# PLL.net
KiCad netlist of a schematic drawn in Altium Designer
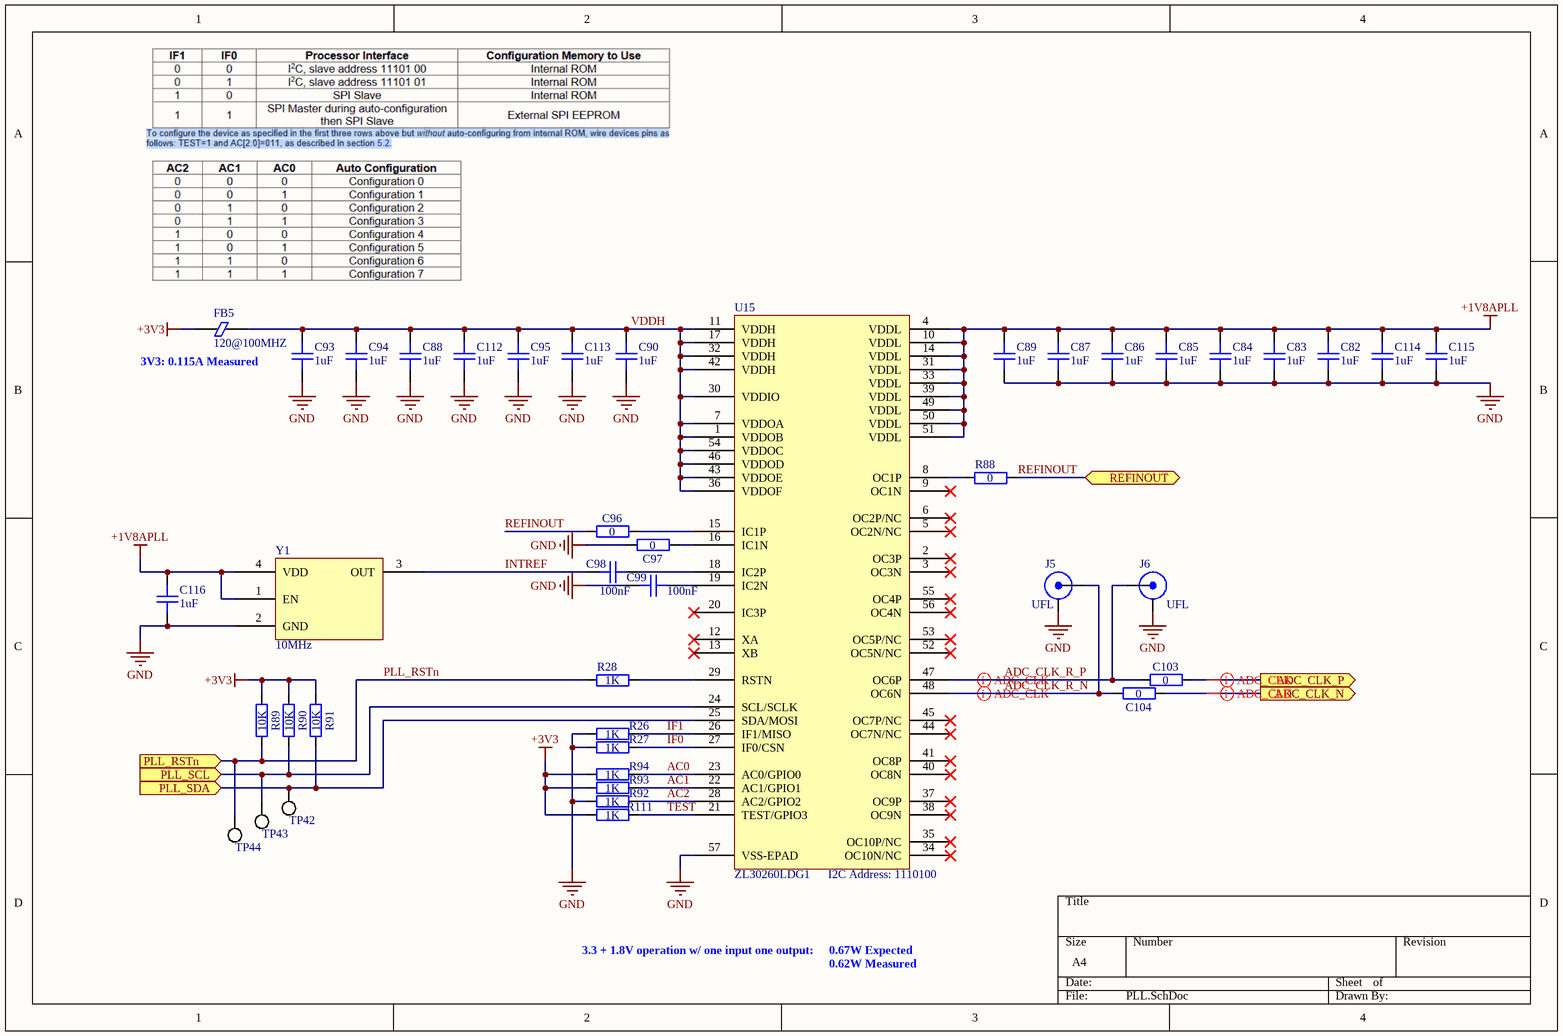
[diagram p0: PLL.SchDoc]

(export (version "E")
  (design (tool "Eeschema 10.0.6"))
  (components
    (comp (ref "C82")
      (value "1uF")
      (footprint "GEN_C_0402")
      (fields
        (field (name "MANUFACTURER") "Murata")
        (field (name "MANUFACTURER PART NUMBER") "GRM155R61E105KA12D")
      )
      (libsource (lib "DSO") (part "CAP 1uF 25V X5R 0402"))
    )
    (comp (ref "C83")
      (value "1uF")
      (footprint "GEN_C_0402")
      (fields
        (field (name "MANUFACTURER") "Murata")
        (field (name "MANUFACTURER PART NUMBER") "GRM155R61E105KA12D")
      )
      (libsource (lib "DSO") (part "CAP 1uF 25V X5R 0402"))
    )
    (comp (ref "C84")
      (value "1uF")
      (footprint "GEN_C_0402")
      (fields
        (field (name "MANUFACTURER") "Murata")
        (field (name "MANUFACTURER PART NUMBER") "GRM155R61E105KA12D")
      )
      (libsource (lib "DSO") (part "CAP 1uF 25V X5R 0402"))
    )
    (comp (ref "C85")
      (value "1uF")
      (footprint "GEN_C_0402")
      (fields
        (field (name "MANUFACTURER") "Murata")
        (field (name "MANUFACTURER PART NUMBER") "GRM155R61E105KA12D")
      )
      (libsource (lib "DSO") (part "CAP 1uF 25V X5R 0402"))
    )
    (comp (ref "C86")
      (value "1uF")
      (footprint "GEN_C_0402")
      (fields
        (field (name "MANUFACTURER") "Murata")
        (field (name "MANUFACTURER PART NUMBER") "GRM155R61E105KA12D")
      )
      (libsource (lib "DSO") (part "CAP 1uF 25V X5R 0402"))
    )
    (comp (ref "C87")
      (value "1uF")
      (footprint "GEN_C_0402")
      (fields
        (field (name "MANUFACTURER") "Murata")
        (field (name "MANUFACTURER PART NUMBER") "GRM155R61E105KA12D")
      )
      (libsource (lib "DSO") (part "CAP 1uF 25V X5R 0402"))
    )
    (comp (ref "C88")
      (value "1uF")
      (footprint "GEN_C_0402")
      (fields
        (field (name "MANUFACTURER") "Murata")
        (field (name "MANUFACTURER PART NUMBER") "GRM155R61E105KA12D")
      )
      (libsource (lib "DSO") (part "CAP 1uF 25V X5R 0402"))
    )
    (comp (ref "C89")
      (value "1uF")
      (footprint "GEN_C_0402")
      (fields
        (field (name "MANUFACTURER") "Murata")
        (field (name "MANUFACTURER PART NUMBER") "GRM155R61E105KA12D")
      )
      (libsource (lib "DSO") (part "CAP 1uF 25V X5R 0402"))
    )
    (comp (ref "C90")
      (value "1uF")
      (footprint "GEN_C_0402")
      (fields
        (field (name "MANUFACTURER") "Murata")
        (field (name "MANUFACTURER PART NUMBER") "GRM155R61E105KA12D")
      )
      (libsource (lib "DSO") (part "CAP 1uF 25V X5R 0402"))
    )
    (comp (ref "C93")
      (value "1uF")
      (footprint "GEN_C_0402")
      (fields
        (field (name "MANUFACTURER") "Murata")
        (field (name "MANUFACTURER PART NUMBER") "GRM155R61E105KA12D")
      )
      (libsource (lib "DSO") (part "CAP 1uF 25V X5R 0402"))
    )
    (comp (ref "C94")
      (value "1uF")
      (footprint "GEN_C_0402")
      (fields
        (field (name "MANUFACTURER") "Murata")
        (field (name "MANUFACTURER PART NUMBER") "GRM155R61E105KA12D")
      )
      (libsource (lib "DSO") (part "CAP 1uF 25V X5R 0402"))
    )
    (comp (ref "C95")
      (value "1uF")
      (footprint "GEN_C_0402")
      (fields
        (field (name "MANUFACTURER") "Murata")
        (field (name "MANUFACTURER PART NUMBER") "GRM155R61E105KA12D")
      )
      (libsource (lib "DSO") (part "CAP 1uF 25V X5R 0402"))
    )
    (comp (ref "C96")
      (value "0")
      (footprint "GEN_R_0402")
      (fields
        (field (name "MANUFACTURER") "Yageo")
        (field (name "MANUFACTURER PART NUMBER") "RC0402JR-070RL")
      )
      (libsource (lib "DSO") (part "RES 0 OHM 1/16W 0402"))
    )
    (comp (ref "C97")
      (value "0")
      (footprint "GEN_R_0402")
      (fields
        (field (name "MANUFACTURER") "Yageo")
        (field (name "MANUFACTURER PART NUMBER") "RC0402JR-070RL")
      )
      (libsource (lib "DSO") (part "RES 0 OHM 1/16W 0402"))
    )
    (comp (ref "C98")
      (value "100nF")
      (footprint "GEN_C_0402")
      (fields
        (field (name "HOUSE PART NUMBER") "C-100nF-0402-002")
        (field (name "MANUFACTURER") "Murata")
        (field (name "MANUFACTURER PART NUMBER") "GCM155R71C104KA55D")
      )
      (libsource (lib "DSO") (part "CAP 100nF 16V X7R 0402"))
    )
    (comp (ref "C99")
      (value "100nF")
      (footprint "GEN_C_0402")
      (fields
        (field (name "HOUSE PART NUMBER") "C-100nF-0402-002")
        (field (name "MANUFACTURER") "Murata")
        (field (name "MANUFACTURER PART NUMBER") "GCM155R71C104KA55D")
      )
      (libsource (lib "DSO") (part "CAP 100nF 16V X7R 0402"))
    )
    (comp (ref "C103")
      (value "0")
      (footprint "GEN_R_0402")
      (fields
        (field (name "MANUFACTURER") "Yageo")
        (field (name "MANUFACTURER PART NUMBER") "RC0402JR-070RL")
      )
      (libsource (lib "DSO") (part "RES 0 OHM 1/16W 0402"))
    )
    (comp (ref "C104")
      (value "0")
      (footprint "GEN_R_0402")
      (fields
        (field (name "MANUFACTURER") "Yageo")
        (field (name "MANUFACTURER PART NUMBER") "RC0402JR-070RL")
      )
      (libsource (lib "DSO") (part "RES 0 OHM 1/16W 0402"))
    )
    (comp (ref "C112")
      (value "1uF")
      (footprint "GEN_C_0402")
      (fields
        (field (name "MANUFACTURER") "Murata")
        (field (name "MANUFACTURER PART NUMBER") "GRM155R61E105KA12D")
      )
      (libsource (lib "DSO") (part "CAP 1uF 25V X5R 0402"))
    )
    (comp (ref "C113")
      (value "1uF")
      (footprint "GEN_C_0402")
      (fields
        (field (name "MANUFACTURER") "Murata")
        (field (name "MANUFACTURER PART NUMBER") "GRM155R61E105KA12D")
      )
      (libsource (lib "DSO") (part "CAP 1uF 25V X5R 0402"))
    )
    (comp (ref "C114")
      (value "1uF")
      (footprint "GEN_C_0402")
      (fields
        (field (name "MANUFACTURER") "Murata")
        (field (name "MANUFACTURER PART NUMBER") "GRM155R61E105KA12D")
      )
      (libsource (lib "DSO") (part "CAP 1uF 25V X5R 0402"))
    )
    (comp (ref "C115")
      (value "1uF")
      (footprint "GEN_C_0402")
      (fields
        (field (name "MANUFACTURER") "Murata")
        (field (name "MANUFACTURER PART NUMBER") "GRM155R61E105KA12D")
      )
      (libsource (lib "DSO") (part "CAP 1uF 25V X5R 0402"))
    )
    (comp (ref "C116")
      (value "1uF")
      (footprint "GEN_C_0402")
      (fields
        (field (name "MANUFACTURER") "Murata")
        (field (name "MANUFACTURER PART NUMBER") "GRM155R61E105KA12D")
      )
      (libsource (lib "DSO") (part "CAP 1uF 25V X5R 0402"))
    )
    (comp (ref "FB5")
      (value "120@100MHZ")
      (footprint "GEN_R_0402")
      (fields (field (name "HOUSE PART NUMBER") "BLM15PX121SN1D") (field (name "MANUFACTURER") "Murata"))
      (libsource (lib "DSO") (part "FERRITE BEAD 120 OHM 0402"))
    )
    (comp (ref "J5")
      (value "UFL")
      (footprint "TE_2334884-1")
      (fields
        (field (name "MANUFACTURER") "TE Connectivity")
        (field (name "MANUFACTURER PART NUMBER") "2334884-1")
      )
      (libsource (lib "DSO") (part "UFL Jack SMD"))
    )
    (comp (ref "J6")
      (value "UFL")
      (footprint "TE_2334884-1")
      (fields
        (field (name "MANUFACTURER") "TE Connectivity")
        (field (name "MANUFACTURER PART NUMBER") "2334884-1")
      )
      (libsource (lib "DSO") (part "UFL Jack SMD"))
    )
    (comp (ref "R26")
      (value "1K")
      (footprint "GEN_R_0402")
      (fields
        (field (name "TOLERANCE") "1%")
        (field (name "MANUFACTURER") "Yageo")
        (field (name "HOUSE PART NUMBER") "R-1K-0402-1%-001")
      )
      (libsource (lib "DSO") (part "RES 1K OHM 1% 1/10W 0402"))
    )
    (comp (ref "R27")
      (value "1K")
      (footprint "GEN_R_0402")
      (fields
        (field (name "TOLERANCE") "1%")
        (field (name "MANUFACTURER") "Yageo")
        (field (name "HOUSE PART NUMBER") "R-1K-0402-1%-001")
      )
      (libsource (lib "DSO") (part "RES 1K OHM 1% 1/10W 0402"))
    )
    (comp (ref "R28")
      (value "1K")
      (footprint "GEN_R_0402")
      (fields
        (field (name "TOLERANCE") "1%")
        (field (name "MANUFACTURER") "Yageo")
        (field (name "HOUSE PART NUMBER") "R-1K-0402-1%-001")
      )
      (libsource (lib "") (part "RES 1K OHM 1% 1/10W 0402_1"))
    )
    (comp (ref "R88")
      (value "0")
      (footprint "GEN_R_0402")
      (fields
        (field (name "MANUFACTURER") "Yageo")
        (field (name "MANUFACTURER PART NUMBER") "RC0402JR-070RL")
      )
      (libsource (lib "") (part "RES 0 OHM 1/16W 0402_1"))
    )
    (comp (ref "R89")
      (value "10K")
      (footprint "GEN_R_0402")
      (fields
        (field (name "TOLERANCE") "1%")
        (field (name "MANUFACTURER") "Panasonic")
        (field (name "MANUFACTURER PART NUMBER") "ERJ-2RKF1002X")
      )
      (libsource (lib "DSO") (part "RES 10K OHM 1% 1/10W 0402"))
    )
    (comp (ref "R90")
      (value "10K")
      (footprint "GEN_R_0402")
      (fields
        (field (name "TOLERANCE") "1%")
        (field (name "MANUFACTURER") "Panasonic")
        (field (name "MANUFACTURER PART NUMBER") "ERJ-2RKF1002X")
      )
      (libsource (lib "DSO") (part "RES 10K OHM 1% 1/10W 0402"))
    )
    (comp (ref "R91")
      (value "10K")
      (footprint "GEN_R_0402")
      (fields
        (field (name "TOLERANCE") "1%")
        (field (name "MANUFACTURER") "Panasonic")
        (field (name "MANUFACTURER PART NUMBER") "ERJ-2RKF1002X")
      )
      (libsource (lib "DSO") (part "RES 10K OHM 1% 1/10W 0402"))
    )
    (comp (ref "R92")
      (value "1K")
      (footprint "GEN_R_0402")
      (fields
        (field (name "TOLERANCE") "1%")
        (field (name "MANUFACTURER") "Yageo")
        (field (name "HOUSE PART NUMBER") "R-1K-0402-1%-001")
      )
      (libsource (lib "DSO") (part "RES 1K OHM 1% 1/10W 0402"))
    )
    (comp (ref "R93")
      (value "1K")
      (footprint "GEN_R_0402")
      (fields
        (field (name "TOLERANCE") "1%")
        (field (name "MANUFACTURER") "Yageo")
        (field (name "HOUSE PART NUMBER") "R-1K-0402-1%-001")
      )
      (libsource (lib "DSO") (part "RES 1K OHM 1% 1/10W 0402"))
    )
    (comp (ref "R94")
      (value "1K")
      (footprint "GEN_R_0402")
      (fields
        (field (name "TOLERANCE") "1%")
        (field (name "MANUFACTURER") "Yageo")
        (field (name "HOUSE PART NUMBER") "R-1K-0402-1%-001")
      )
      (libsource (lib "DSO") (part "RES 1K OHM 1% 1/10W 0402"))
    )
    (comp (ref "R111")
      (value "1K")
      (footprint "GEN_R_0402")
      (fields
        (field (name "TOLERANCE") "1%")
        (field (name "MANUFACTURER") "Yageo")
        (field (name "HOUSE PART NUMBER") "R-1K-0402-1%-001")
      )
      (libsource (lib "DSO") (part "RES 1K OHM 1% 1/10W 0402"))
    )
    (comp (ref "TP42") (value "PCB") (footprint "GEN_TP_PCB") (libsource (lib "DSO") (part "TP PCB 1mm")))
    (comp (ref "TP43") (value "PCB") (footprint "GEN_TP_PCB") (libsource (lib "DSO") (part "TP PCB 1mm")))
    (comp (ref "TP44") (value "PCB") (footprint "GEN_TP_PCB") (libsource (lib "DSO") (part "TP PCB 1mm")))
    (comp (ref "U15")
      (value "ZL30260LDG1")
      (footprint "MC_QFN56_ZL30260")
      (fields (field (name "MANUFACTURER") "Microchip"))
      (libsource (lib "DSO") (part "IC CLK GEN ZL30260LDG1"))
    )
    (comp (ref "Y1")
      (value "10MHz")
      (footprint "ECS_TXO-3225")
      (fields
        (field (name "MANUFACTURER") "ECS International")
        (field (name "MANUFACTURER PART NUMBER") "ECS-TXO-3225MV-100-TR")
      )
      (libsource (lib "DSO") (part "OSC 10MHz ECS-TXO-3225MV"))
    )
  )
  (nets
    (net (code "1") (name "+1V8APLL") (class "Default")
      (node (ref "C114") (pin "1") (pinfunction "1_1") (pintype "passive"))
      (node (ref "C115") (pin "1") (pinfunction "1_1") (pintype "passive"))
      (node (ref "C116") (pin "1") (pinfunction "1_1") (pintype "passive"))
      (node (ref "C82") (pin "1") (pinfunction "1_1") (pintype "passive"))
      (node (ref "C83") (pin "1") (pinfunction "1_1") (pintype "passive"))
      (node (ref "C84") (pin "1") (pinfunction "1_1") (pintype "passive"))
      (node (ref "C85") (pin "1") (pinfunction "1_1") (pintype "passive"))
      (node (ref "C86") (pin "1") (pinfunction "1_1") (pintype "passive"))
      (node (ref "C87") (pin "1") (pinfunction "1_1") (pintype "passive"))
      (node (ref "C89") (pin "1") (pinfunction "1_1") (pintype "passive"))
      (node (ref "U15") (pin "10") (pinfunction "VDDL_10") (pintype "passive"))
      (node (ref "U15") (pin "14") (pinfunction "VDDL_14") (pintype "passive"))
      (node (ref "U15") (pin "31") (pinfunction "VDDL_31") (pintype "passive"))
      (node (ref "U15") (pin "33") (pinfunction "VDDL_33") (pintype "passive"))
      (node (ref "U15") (pin "39") (pinfunction "VDDL_39") (pintype "passive"))
      (node (ref "U15") (pin "4") (pinfunction "VDDL_4") (pintype "passive"))
      (node (ref "U15") (pin "49") (pinfunction "VDDL_49") (pintype "passive"))
      (node (ref "U15") (pin "50") (pinfunction "VDDL_50") (pintype "passive"))
      (node (ref "U15") (pin "51") (pinfunction "VDDL_51") (pintype "passive"))
      (node (ref "Y1") (pin "1") (pinfunction "EN_1") (pintype "passive"))
      (node (ref "Y1") (pin "4") (pinfunction "VDD_4") (pintype "power_in"))
    )
    (net (code "2") (name "+3V3") (class "Default")
      (node (ref "FB5") (pin "1") (pinfunction "1_1") (pintype "passive"))
      (node (ref "R111") (pin "1") (pinfunction "1_1") (pintype "passive"))
      (node (ref "R89") (pin "2") (pinfunction "2_2") (pintype "passive"))
      (node (ref "R90") (pin "2") (pinfunction "2_2") (pintype "passive"))
      (node (ref "R91") (pin "2") (pinfunction "2_2") (pintype "passive"))
      (node (ref "R93") (pin "1") (pinfunction "1_1") (pintype "passive"))
      (node (ref "R94") (pin "1") (pinfunction "1_1") (pintype "passive"))
    )
    (net (code "3") (name "/AC0") (class "Default")
      (node (ref "R94") (pin "2") (pinfunction "2_2") (pintype "passive"))
      (node (ref "U15") (pin "23") (pinfunction "AC0/GPIO0_23") (pintype "passive"))
    )
    (net (code "4") (name "/AC1") (class "Default")
      (node (ref "R93") (pin "2") (pinfunction "2_2") (pintype "passive"))
      (node (ref "U15") (pin "22") (pinfunction "AC1/GPIO1_22") (pintype "passive"))
    )
    (net (code "5") (name "/AC2") (class "Default")
      (node (ref "R92") (pin "2") (pinfunction "2_2") (pintype "passive"))
      (node (ref "U15") (pin "28") (pinfunction "AC2/GPIO2_28") (pintype "passive"))
    )
    (net (code "6") (name "/ADC_CLK_N") (class "Default")
      (node (ref "C104") (pin "1") (pinfunction "1_1") (pintype "passive"))
    )
    (net (code "7") (name "/ADC_CLK_P") (class "Default")
      (node (ref "C103") (pin "1") (pinfunction "1_1") (pintype "passive"))
    )
    (net (code "8") (name "/ADC_CLK_R_N") (class "Default")
      (node (ref "C104") (pin "2") (pinfunction "2_2") (pintype "passive"))
      (node (ref "J5") (pin "1") (pinfunction "Signal_1") (pintype "passive"))
      (node (ref "U15") (pin "48") (pinfunction "OC6N_48") (pintype "passive"))
    )
    (net (code "9") (name "/ADC_CLK_R_P") (class "Default")
      (node (ref "C103") (pin "2") (pinfunction "2_2") (pintype "passive"))
      (node (ref "J6") (pin "1") (pinfunction "Signal_1") (pintype "passive"))
      (node (ref "U15") (pin "47") (pinfunction "OC6P_47") (pintype "passive"))
    )
    (net (code "10") (name "/IF0") (class "Default")
      (node (ref "R27") (pin "2") (pinfunction "2_2") (pintype "passive"))
      (node (ref "U15") (pin "27") (pinfunction "IF0/CSN_27") (pintype "passive"))
    )
    (net (code "11") (name "/IF1") (class "Default")
      (node (ref "R26") (pin "2") (pinfunction "2_2") (pintype "passive"))
      (node (ref "U15") (pin "26") (pinfunction "IF1/MISO_26") (pintype "passive"))
    )
    (net (code "12") (name "/INTREF") (class "Default")
      (node (ref "C98") (pin "2") (pinfunction "2_2") (pintype "passive"))
      (node (ref "Y1") (pin "3") (pinfunction "OUT_3") (pintype "passive"))
    )
    (net (code "13") (name "/PLL_RSTn") (class "Default")
      (node (ref "R28") (pin "2") (pinfunction "2_2") (pintype "passive"))
      (node (ref "R89") (pin "1") (pinfunction "1_1") (pintype "passive"))
      (node (ref "TP44") (pin "1") (pinfunction "1_1") (pintype "passive"))
    )
    (net (code "14") (name "/PLL_SCL") (class "Default")
      (node (ref "R90") (pin "1") (pinfunction "1_1") (pintype "passive"))
      (node (ref "TP43") (pin "1") (pinfunction "1_1") (pintype "passive"))
      (node (ref "U15") (pin "24") (pinfunction "SCL/SCLK_24") (pintype "passive"))
    )
    (net (code "15") (name "/PLL_SDA") (class "Default")
      (node (ref "R91") (pin "1") (pinfunction "1_1") (pintype "passive"))
      (node (ref "TP42") (pin "1") (pinfunction "1_1") (pintype "passive"))
      (node (ref "U15") (pin "25") (pinfunction "SDA/MOSI_25") (pintype "passive"))
    )
    (net (code "16") (name "/REFINOUT") (class "Default")
      (node (ref "C96") (pin "2") (pinfunction "2_2") (pintype "passive"))
      (node (ref "R88") (pin "2") (pinfunction "2_2") (pintype "passive"))
    )
    (net (code "17") (name "/TEST") (class "Default")
      (node (ref "R111") (pin "2") (pinfunction "2_2") (pintype "passive"))
      (node (ref "U15") (pin "21") (pinfunction "TEST/GPIO3_21") (pintype "passive"))
    )
    (net (code "18") (name "/VDDH") (class "Default")
      (node (ref "C112") (pin "1") (pinfunction "1_1") (pintype "passive"))
      (node (ref "C113") (pin "1") (pinfunction "1_1") (pintype "passive"))
      (node (ref "C88") (pin "1") (pinfunction "1_1") (pintype "passive"))
      (node (ref "C90") (pin "1") (pinfunction "1_1") (pintype "passive"))
      (node (ref "C93") (pin "1") (pinfunction "1_1") (pintype "passive"))
      (node (ref "C94") (pin "1") (pinfunction "1_1") (pintype "passive"))
      (node (ref "C95") (pin "1") (pinfunction "1_1") (pintype "passive"))
      (node (ref "FB5") (pin "2") (pinfunction "2_2") (pintype "passive"))
      (node (ref "U15") (pin "1") (pinfunction "VDDOB_1") (pintype "passive"))
      (node (ref "U15") (pin "11") (pinfunction "VDDH_11") (pintype "passive"))
      (node (ref "U15") (pin "17") (pinfunction "VDDH_17") (pintype "passive"))
      (node (ref "U15") (pin "30") (pinfunction "VDDIO_30") (pintype "passive"))
      (node (ref "U15") (pin "32") (pinfunction "VDDH_32") (pintype "passive"))
      (node (ref "U15") (pin "36") (pinfunction "VDDOF_36") (pintype "passive"))
      (node (ref "U15") (pin "42") (pinfunction "VDDH_42") (pintype "passive"))
      (node (ref "U15") (pin "43") (pinfunction "VDDOE_43") (pintype "passive"))
      (node (ref "U15") (pin "46") (pinfunction "VDDOD_46") (pintype "passive"))
      (node (ref "U15") (pin "54") (pinfunction "VDDOC_54") (pintype "passive"))
      (node (ref "U15") (pin "7") (pinfunction "VDDOA_7") (pintype "passive"))
    )
    (net (code "19") (name "GND") (class "Default")
      (node (ref "C112") (pin "2") (pinfunction "2_2") (pintype "passive"))
      (node (ref "C113") (pin "2") (pinfunction "2_2") (pintype "passive"))
      (node (ref "C114") (pin "2") (pinfunction "2_2") (pintype "passive"))
      (node (ref "C115") (pin "2") (pinfunction "2_2") (pintype "passive"))
      (node (ref "C116") (pin "2") (pinfunction "2_2") (pintype "passive"))
      (node (ref "C82") (pin "2") (pinfunction "2_2") (pintype "passive"))
      (node (ref "C83") (pin "2") (pinfunction "2_2") (pintype "passive"))
      (node (ref "C84") (pin "2") (pinfunction "2_2") (pintype "passive"))
      (node (ref "C85") (pin "2") (pinfunction "2_2") (pintype "passive"))
      (node (ref "C86") (pin "2") (pinfunction "2_2") (pintype "passive"))
      (node (ref "C87") (pin "2") (pinfunction "2_2") (pintype "passive"))
      (node (ref "C88") (pin "2") (pinfunction "2_2") (pintype "passive"))
      (node (ref "C89") (pin "2") (pinfunction "2_2") (pintype "passive"))
      (node (ref "C90") (pin "2") (pinfunction "2_2") (pintype "passive"))
      (node (ref "C93") (pin "2") (pinfunction "2_2") (pintype "passive"))
      (node (ref "C94") (pin "2") (pinfunction "2_2") (pintype "passive"))
      (node (ref "C95") (pin "2") (pinfunction "2_2") (pintype "passive"))
      (node (ref "C97") (pin "2") (pinfunction "2_2") (pintype "passive"))
      (node (ref "C99") (pin "2") (pinfunction "2_2") (pintype "passive"))
      (node (ref "J5") (pin "2") (pinfunction "SHIELD_2") (pintype "passive"))
      (node (ref "J6") (pin "2") (pinfunction "SHIELD_2") (pintype "passive"))
      (node (ref "R26") (pin "1") (pinfunction "1_1") (pintype "passive"))
      (node (ref "R27") (pin "1") (pinfunction "1_1") (pintype "passive"))
      (node (ref "R92") (pin "1") (pinfunction "1_1") (pintype "passive"))
      (node (ref "U15") (pin "57") (pinfunction "VSS-EPAD_57") (pintype "passive"))
      (node (ref "Y1") (pin "2") (pinfunction "GND_2") (pintype "power_in"))
    )
    (net (code "20") (name "Net-(U15-IC1N)") (class "Default")
      (node (ref "C97") (pin "1") (pinfunction "1_1") (pintype "passive"))
      (node (ref "U15") (pin "16") (pinfunction "IC1N_16") (pintype "passive"))
    )
    (net (code "21") (name "Net-(U15-IC1P)") (class "Default")
      (node (ref "C96") (pin "1") (pinfunction "1_1") (pintype "passive"))
      (node (ref "U15") (pin "15") (pinfunction "IC1P_15") (pintype "passive"))
    )
    (net (code "22") (name "Net-(U15-IC2N)") (class "Default")
      (node (ref "C99") (pin "1") (pinfunction "1_1") (pintype "passive"))
      (node (ref "U15") (pin "19") (pinfunction "IC2N_19") (pintype "passive"))
    )
    (net (code "23") (name "Net-(U15-IC2P)") (class "Default")
      (node (ref "C98") (pin "1") (pinfunction "1_1") (pintype "passive"))
      (node (ref "U15") (pin "18") (pinfunction "IC2P_18") (pintype "passive"))
    )
    (net (code "24") (name "Net-(U15-OC1P)") (class "Default")
      (node (ref "R88") (pin "1") (pinfunction "1_1") (pintype "passive"))
      (node (ref "U15") (pin "8") (pinfunction "OC1P_8") (pintype "passive"))
    )
    (net (code "25") (name "Net-(U15-RSTN)") (class "Default")
      (node (ref "R28") (pin "1") (pinfunction "1_1") (pintype "passive"))
      (node (ref "U15") (pin "29") (pinfunction "RSTN_29") (pintype "passive"))
    )
    (net (code "26") (name "unconnected-(U15-IC3P-Pad20)") (class "Default")
      (node (ref "U15") (pin "20") (pinfunction "IC3P_20") (pintype "passive+no_connect"))
    )
    (net (code "27") (name "unconnected-(U15-OC1N-Pad9)") (class "Default")
      (node (ref "U15") (pin "9") (pinfunction "OC1N_9") (pintype "passive+no_connect"))
    )
    (net (code "28") (name "unconnected-(U15-OC2N{slash}NC-Pad5)") (class "Default")
      (node (ref "U15") (pin "5") (pinfunction "OC2N/NC_5") (pintype "passive+no_connect"))
    )
    (net (code "29") (name "unconnected-(U15-OC2P{slash}NC-Pad6)") (class "Default")
      (node (ref "U15") (pin "6") (pinfunction "OC2P/NC_6") (pintype "passive+no_connect"))
    )
    (net (code "30") (name "unconnected-(U15-OC3N-Pad3)") (class "Default")
      (node (ref "U15") (pin "3") (pinfunction "OC3N_3") (pintype "passive+no_connect"))
    )
    (net (code "31") (name "unconnected-(U15-OC3P-Pad2)") (class "Default")
      (node (ref "U15") (pin "2") (pinfunction "OC3P_2") (pintype "passive+no_connect"))
    )
    (net (code "32") (name "unconnected-(U15-OC4N-Pad56)") (class "Default")
      (node (ref "U15") (pin "56") (pinfunction "OC4N_56") (pintype "passive+no_connect"))
    )
    (net (code "33") (name "unconnected-(U15-OC4P-Pad55)") (class "Default")
      (node (ref "U15") (pin "55") (pinfunction "OC4P_55") (pintype "passive+no_connect"))
    )
    (net (code "34") (name "unconnected-(U15-OC5N{slash}NC-Pad52)") (class "Default")
      (node (ref "U15") (pin "52") (pinfunction "OC5N/NC_52") (pintype "passive+no_connect"))
    )
    (net (code "35") (name "unconnected-(U15-OC5P{slash}NC-Pad53)") (class "Default")
      (node (ref "U15") (pin "53") (pinfunction "OC5P/NC_53") (pintype "passive+no_connect"))
    )
    (net (code "36") (name "unconnected-(U15-OC7N{slash}NC-Pad44)") (class "Default")
      (node (ref "U15") (pin "44") (pinfunction "OC7N/NC_44") (pintype "passive+no_connect"))
    )
    (net (code "37") (name "unconnected-(U15-OC7P{slash}NC-Pad45)") (class "Default")
      (node (ref "U15") (pin "45") (pinfunction "OC7P/NC_45") (pintype "passive+no_connect"))
    )
    (net (code "38") (name "unconnected-(U15-OC8N-Pad40)") (class "Default")
      (node (ref "U15") (pin "40") (pinfunction "OC8N_40") (pintype "passive+no_connect"))
    )
    (net (code "39") (name "unconnected-(U15-OC8P-Pad41)") (class "Default")
      (node (ref "U15") (pin "41") (pinfunction "OC8P_41") (pintype "passive+no_connect"))
    )
    (net (code "40") (name "unconnected-(U15-OC9N-Pad38)") (class "Default")
      (node (ref "U15") (pin "38") (pinfunction "OC9N_38") (pintype "passive+no_connect"))
    )
    (net (code "41") (name "unconnected-(U15-OC9P-Pad37)") (class "Default")
      (node (ref "U15") (pin "37") (pinfunction "OC9P_37") (pintype "passive+no_connect"))
    )
    (net (code "42") (name "unconnected-(U15-OC10N{slash}NC-Pad34)") (class "Default")
      (node (ref "U15") (pin "34") (pinfunction "OC10N/NC_34") (pintype "passive+no_connect"))
    )
    (net (code "43") (name "unconnected-(U15-OC10P{slash}NC-Pad35)") (class "Default")
      (node (ref "U15") (pin "35") (pinfunction "OC10P/NC_35") (pintype "passive+no_connect"))
    )
    (net (code "44") (name "unconnected-(U15-XA-Pad12)") (class "Default")
      (node (ref "U15") (pin "12") (pinfunction "XA_12") (pintype "passive+no_connect"))
    )
    (net (code "45") (name "unconnected-(U15-XB-Pad13)") (class "Default")
      (node (ref "U15") (pin "13") (pinfunction "XB_13") (pintype "passive+no_connect"))
    )
  )
)
